# NRF24L01_TestbedV1.net
KiCad netlist of a schematic drawn in EAGLE
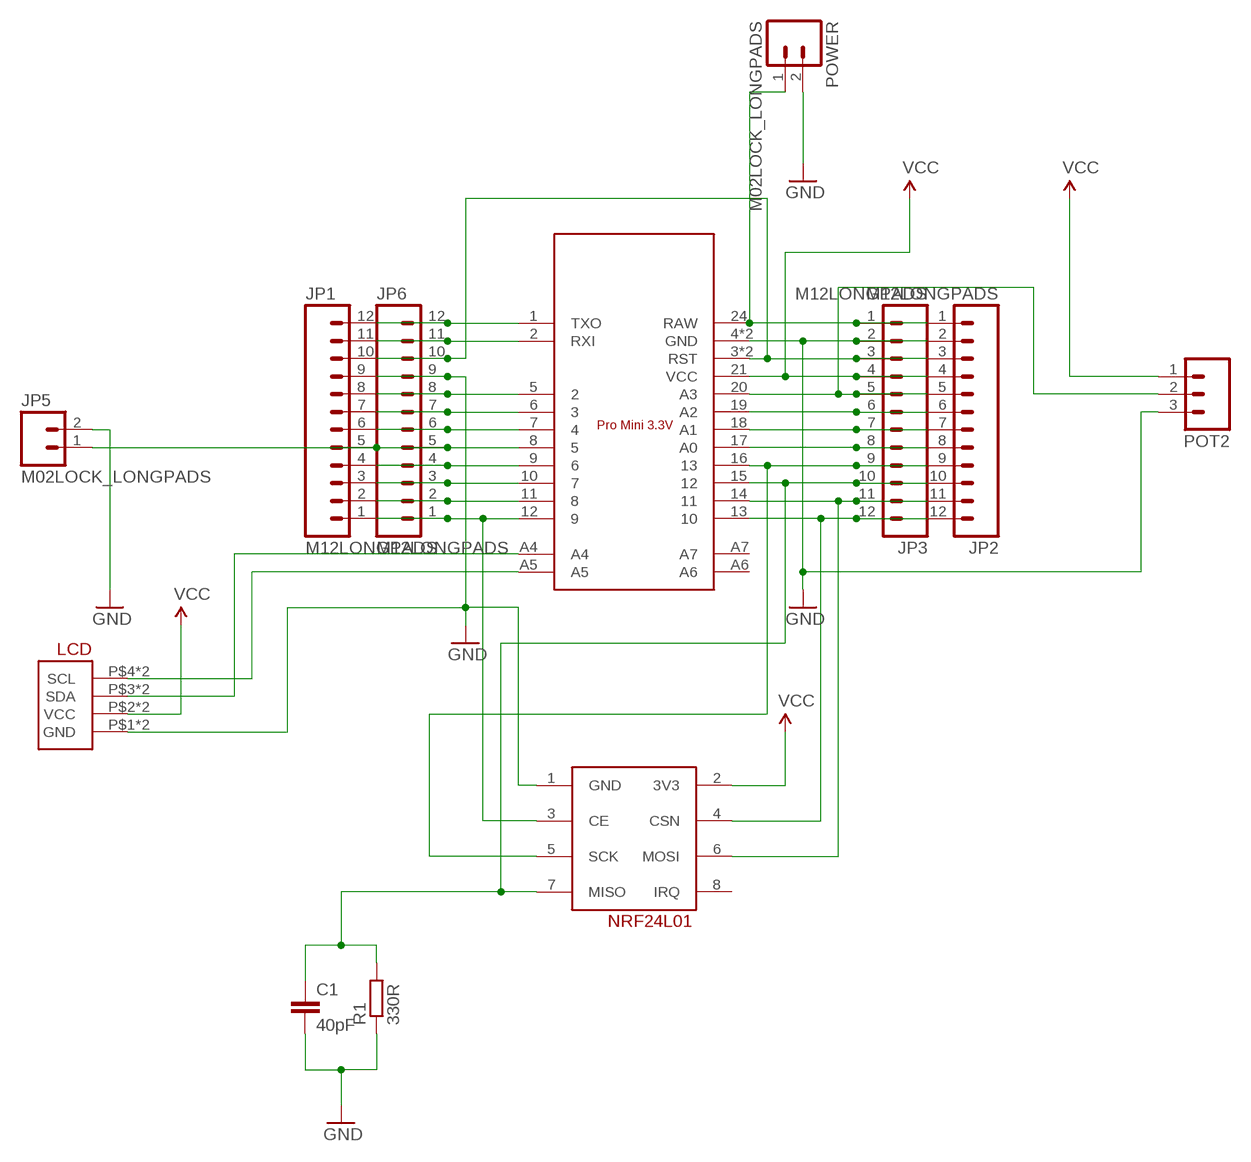
[diagram p0: schematic, sheet 1]

(export (version "E")
  (design (tool "Eeschema 10.0.6"))
  (components
    (comp (ref "C1")
      (value "40pF")
      (footprint "eagle-import:C1206")
      (libsource (lib "eagle-import") (part "C-EUC1206"))
    )
    (comp (ref "JP1")
      (value "M12LONGPADS")
      (footprint "eagle-import:1X12_LONGPADS")
      (libsource (lib "eagle-import") (part "M12LONGPADS"))
    )
    (comp (ref "JP2")
      (value "M12LONGPADS")
      (footprint "eagle-import:1X12_LONGPADS")
      (libsource (lib "eagle-import") (part "M12LONGPADS"))
    )
    (comp (ref "JP3")
      (value "M12LONGPADS")
      (footprint "eagle-import:1X12_LONGPADS")
      (libsource (lib "eagle-import") (part "M12LONGPADS"))
    )
    (comp (ref "JP5")
      (value "M02LOCK_LONGPADS")
      (footprint "eagle-import:1X02_LOCK_LONGPADS")
      (libsource (lib "eagle-import") (part "M02LOCK_LONGPADS"))
    )
    (comp (ref "JP6")
      (value "M12LONGPADS")
      (footprint "eagle-import:1X12_LONGPADS")
      (libsource (lib "eagle-import") (part "M12LONGPADS"))
    )
    (comp (ref "POT2")
      (value "M03LONGPADS")
      (footprint "eagle-import:1X03_LONGPADS")
      (libsource (lib "eagle-import") (part "M03LONGPADS"))
    )
    (comp (ref "POWER")
      (value "M02LOCK_LONGPADS")
      (footprint "eagle-import:1X02_LOCK_LONGPADS")
      (libsource (lib "eagle-import") (part "M02LOCK_LONGPADS"))
    )
    (comp (ref "R1")
      (value "330R")
      (footprint "eagle-import:R1206")
      (libsource (lib "eagle-import") (part "R-EU_R1206"))
    )
    (comp (ref "U$1")
      (value "ARDUINO_PRO_MINI_3V3")
      (footprint "eagle-import:ARDUINO_PRO_MINI_3V3")
      (libsource (lib "eagle-import") (part "ARDUINO_PRO_MINI_3V3"))
    )
    (comp (ref "U$2")
      (value "NRF24L01BOARD")
      (footprint "eagle-import:NRF24L01BOARD")
      (libsource (lib "eagle-import") (part "NRF24L01BOARD"))
    )
    (comp (ref "U$3")
      (value "I2C-LCD")
      (footprint "eagle-import:I2C-LCD")
      (libsource (lib "eagle-import") (part "I2C-LCD"))
    )
  )
  (nets
    (net (code "1") (name "GND") (class "Default")
      (node (ref "C1") (pin "2") (pinfunction "2_2") (pintype "passive"))
      (node (ref "JP1") (pin "9") (pinfunction "9_9") (pintype "passive"))
      (node (ref "JP2") (pin "2") (pinfunction "2_2") (pintype "passive"))
      (node (ref "JP3") (pin "2") (pinfunction "2_2") (pintype "passive"))
      (node (ref "JP5") (pin "2") (pinfunction "2_2") (pintype "passive"))
      (node (ref "JP6") (pin "9") (pinfunction "9_9") (pintype "passive"))
      (node (ref "POT2") (pin "3") (pinfunction "3_3") (pintype "passive"))
      (node (ref "POWER") (pin "2") (pinfunction "2_2") (pintype "passive"))
      (node (ref "R1") (pin "1") (pinfunction "1_1") (pintype "passive"))
      (node (ref "U$1") (pin "23") (pinfunction "GND_23") (pintype "bidirectional"))
      (node (ref "U$1") (pin "4") (pinfunction "GND_4") (pintype "bidirectional"))
      (node (ref "U$2") (pin "1") (pinfunction "GND_1") (pintype "bidirectional"))
      (node (ref "U$3") (pin "P$1") (pinfunction "GND_P$1") (pintype "bidirectional"))
      (node (ref "U$3") (pin "S$1") (pinfunction "GND_S$1") (pintype "bidirectional"))
    )
    (net (code "2") (name "Net-(JP1-Pad10)") (class "Default")
      (node (ref "JP1") (pin "10") (pinfunction "10_10") (pintype "passive"))
      (node (ref "JP2") (pin "3") (pinfunction "3_3") (pintype "passive"))
      (node (ref "JP3") (pin "3") (pinfunction "3_3") (pintype "passive"))
      (node (ref "JP6") (pin "10") (pinfunction "10_10") (pintype "passive"))
      (node (ref "U$1") (pin "22") (pinfunction "RST_22") (pintype "bidirectional"))
      (node (ref "U$1") (pin "3") (pinfunction "RST_3") (pintype "bidirectional"))
    )
    (net (code "3") (name "Net-(U$1-2)") (class "Default")
      (node (ref "JP1") (pin "8") (pinfunction "8_8") (pintype "passive"))
      (node (ref "JP6") (pin "8") (pinfunction "8_8") (pintype "passive"))
      (node (ref "U$1") (pin "5") (pinfunction "2_5") (pintype "bidirectional"))
    )
    (net (code "4") (name "Net-(U$1-3)") (class "Default")
      (node (ref "JP1") (pin "7") (pinfunction "7_7") (pintype "passive"))
      (node (ref "JP6") (pin "7") (pinfunction "7_7") (pintype "passive"))
      (node (ref "U$1") (pin "6") (pinfunction "3_6") (pintype "bidirectional"))
    )
    (net (code "5") (name "Net-(U$1-4)") (class "Default")
      (node (ref "JP1") (pin "6") (pinfunction "6_6") (pintype "passive"))
      (node (ref "JP6") (pin "6") (pinfunction "6_6") (pintype "passive"))
      (node (ref "U$1") (pin "7") (pinfunction "4_7") (pintype "bidirectional"))
    )
    (net (code "6") (name "Net-(U$1-5)") (class "Default")
      (node (ref "JP1") (pin "5") (pinfunction "5_5") (pintype "passive"))
      (node (ref "JP5") (pin "1") (pinfunction "1_1") (pintype "passive"))
      (node (ref "JP6") (pin "5") (pinfunction "5_5") (pintype "passive"))
      (node (ref "U$1") (pin "8") (pinfunction "5_8") (pintype "bidirectional"))
    )
    (net (code "7") (name "Net-(U$1-6)") (class "Default")
      (node (ref "JP1") (pin "4") (pinfunction "4_4") (pintype "passive"))
      (node (ref "JP6") (pin "4") (pinfunction "4_4") (pintype "passive"))
      (node (ref "U$1") (pin "9") (pinfunction "6_9") (pintype "bidirectional"))
    )
    (net (code "8") (name "Net-(U$1-7)") (class "Default")
      (node (ref "JP1") (pin "3") (pinfunction "3_3") (pintype "passive"))
      (node (ref "JP6") (pin "3") (pinfunction "3_3") (pintype "passive"))
      (node (ref "U$1") (pin "10") (pinfunction "7_10") (pintype "bidirectional"))
    )
    (net (code "9") (name "Net-(U$1-8)") (class "Default")
      (node (ref "JP1") (pin "2") (pinfunction "2_2") (pintype "passive"))
      (node (ref "JP6") (pin "2") (pinfunction "2_2") (pintype "passive"))
      (node (ref "U$1") (pin "11") (pinfunction "8_11") (pintype "bidirectional"))
    )
    (net (code "10") (name "Net-(U$1-9)") (class "Default")
      (node (ref "JP1") (pin "1") (pinfunction "1_1") (pintype "passive"))
      (node (ref "JP6") (pin "1") (pinfunction "1_1") (pintype "passive"))
      (node (ref "U$1") (pin "12") (pinfunction "9_12") (pintype "bidirectional"))
      (node (ref "U$2") (pin "3") (pinfunction "CE_3") (pintype "bidirectional"))
    )
    (net (code "11") (name "Net-(U$1-10)") (class "Default")
      (node (ref "JP2") (pin "12") (pinfunction "12_12") (pintype "passive"))
      (node (ref "JP3") (pin "12") (pinfunction "12_12") (pintype "passive"))
      (node (ref "U$1") (pin "13") (pinfunction "10_13") (pintype "bidirectional"))
      (node (ref "U$2") (pin "4") (pinfunction "CSN_4") (pintype "bidirectional"))
    )
    (net (code "12") (name "Net-(U$1-11)") (class "Default")
      (node (ref "JP2") (pin "11") (pinfunction "11_11") (pintype "passive"))
      (node (ref "JP3") (pin "11") (pinfunction "11_11") (pintype "passive"))
      (node (ref "U$1") (pin "14") (pinfunction "11_14") (pintype "bidirectional"))
      (node (ref "U$2") (pin "6") (pinfunction "MOSI_6") (pintype "bidirectional"))
    )
    (net (code "13") (name "Net-(U$1-12)") (class "Default")
      (node (ref "C1") (pin "1") (pinfunction "1_1") (pintype "passive"))
      (node (ref "JP2") (pin "10") (pinfunction "10_10") (pintype "passive"))
      (node (ref "JP3") (pin "10") (pinfunction "10_10") (pintype "passive"))
      (node (ref "R1") (pin "2") (pinfunction "2_2") (pintype "passive"))
      (node (ref "U$1") (pin "15") (pinfunction "12_15") (pintype "bidirectional"))
      (node (ref "U$2") (pin "7") (pinfunction "MISO_7") (pintype "bidirectional"))
    )
    (net (code "14") (name "Net-(U$1-13)") (class "Default")
      (node (ref "JP2") (pin "9") (pinfunction "9_9") (pintype "passive"))
      (node (ref "JP3") (pin "9") (pinfunction "9_9") (pintype "passive"))
      (node (ref "U$1") (pin "16") (pinfunction "13_16") (pintype "bidirectional"))
      (node (ref "U$2") (pin "5") (pinfunction "SCK_5") (pintype "bidirectional"))
    )
    (net (code "15") (name "Net-(U$1-A0)") (class "Default")
      (node (ref "JP2") (pin "8") (pinfunction "8_8") (pintype "passive"))
      (node (ref "JP3") (pin "8") (pinfunction "8_8") (pintype "passive"))
      (node (ref "U$1") (pin "17") (pinfunction "A0_17") (pintype "bidirectional"))
    )
    (net (code "16") (name "Net-(U$1-A1)") (class "Default")
      (node (ref "JP2") (pin "7") (pinfunction "7_7") (pintype "passive"))
      (node (ref "JP3") (pin "7") (pinfunction "7_7") (pintype "passive"))
      (node (ref "U$1") (pin "18") (pinfunction "A1_18") (pintype "bidirectional"))
    )
    (net (code "17") (name "Net-(U$1-A2)") (class "Default")
      (node (ref "JP2") (pin "6") (pinfunction "6_6") (pintype "passive"))
      (node (ref "JP3") (pin "6") (pinfunction "6_6") (pintype "passive"))
      (node (ref "U$1") (pin "19") (pinfunction "A2_19") (pintype "bidirectional"))
    )
    (net (code "18") (name "Net-(U$1-A3)") (class "Default")
      (node (ref "JP2") (pin "5") (pinfunction "5_5") (pintype "passive"))
      (node (ref "JP3") (pin "5") (pinfunction "5_5") (pintype "passive"))
      (node (ref "POT2") (pin "2") (pinfunction "2_2") (pintype "passive"))
      (node (ref "U$1") (pin "20") (pinfunction "A3_20") (pintype "bidirectional"))
    )
    (net (code "19") (name "Net-(U$1-PadA4)") (class "Default")
      (node (ref "U$1") (pin "A4") (pinfunction "A4_A4") (pintype "bidirectional"))
      (node (ref "U$3") (pin "P$3") (pinfunction "SDA_P$3") (pintype "bidirectional"))
      (node (ref "U$3") (pin "S$3") (pinfunction "SDA_S$3") (pintype "bidirectional"))
    )
    (net (code "20") (name "Net-(U$1-PadA5)") (class "Default")
      (node (ref "U$1") (pin "A5") (pinfunction "A5_A5") (pintype "bidirectional"))
      (node (ref "U$3") (pin "P$4") (pinfunction "SCL_P$4") (pintype "bidirectional"))
      (node (ref "U$3") (pin "S$4") (pinfunction "SCL_S$4") (pintype "bidirectional"))
    )
    (net (code "21") (name "Net-(U$1-RAW)") (class "Default")
      (node (ref "JP2") (pin "1") (pinfunction "1_1") (pintype "passive"))
      (node (ref "JP3") (pin "1") (pinfunction "1_1") (pintype "passive"))
      (node (ref "POWER") (pin "1") (pinfunction "1_1") (pintype "passive"))
      (node (ref "U$1") (pin "24") (pinfunction "RAW_24") (pintype "bidirectional"))
    )
    (net (code "22") (name "Net-(U$1-RXI)") (class "Default")
      (node (ref "JP1") (pin "11") (pinfunction "11_11") (pintype "passive"))
      (node (ref "JP6") (pin "11") (pinfunction "11_11") (pintype "passive"))
      (node (ref "U$1") (pin "2") (pinfunction "RXI_2") (pintype "bidirectional"))
    )
    (net (code "23") (name "Net-(U$1-TXO)") (class "Default")
      (node (ref "JP1") (pin "12") (pinfunction "12_12") (pintype "passive"))
      (node (ref "JP6") (pin "12") (pinfunction "12_12") (pintype "passive"))
      (node (ref "U$1") (pin "1") (pinfunction "TXO_1") (pintype "bidirectional"))
    )
    (net (code "24") (name "VCC") (class "Default")
      (node (ref "JP2") (pin "4") (pinfunction "4_4") (pintype "passive"))
      (node (ref "JP3") (pin "4") (pinfunction "4_4") (pintype "passive"))
      (node (ref "POT2") (pin "1") (pinfunction "1_1") (pintype "passive"))
      (node (ref "U$1") (pin "21") (pinfunction "VCC_21") (pintype "bidirectional"))
      (node (ref "U$2") (pin "2") (pinfunction "3V3_2") (pintype "bidirectional"))
      (node (ref "U$3") (pin "P$2") (pinfunction "VCC_P$2") (pintype "bidirectional"))
      (node (ref "U$3") (pin "S$2") (pinfunction "VCC_S$2") (pintype "bidirectional"))
    )
    (net (code "25") (name "unconnected-(U$1-PadA6)") (class "Default")
      (node (ref "U$1") (pin "A6") (pinfunction "A6_A6") (pintype "bidirectional"))
    )
    (net (code "26") (name "unconnected-(U$1-PadA7)") (class "Default")
      (node (ref "U$1") (pin "A7") (pinfunction "A7_A7") (pintype "bidirectional"))
    )
    (net (code "27") (name "unconnected-(U$2-IRQ-Pad8)") (class "Default")
      (node (ref "U$2") (pin "8") (pinfunction "IRQ_8") (pintype "bidirectional"))
    )
  )
)
